# ESP-12E_Breakout_SMT.net
KiCad netlist of a schematic drawn in EAGLE
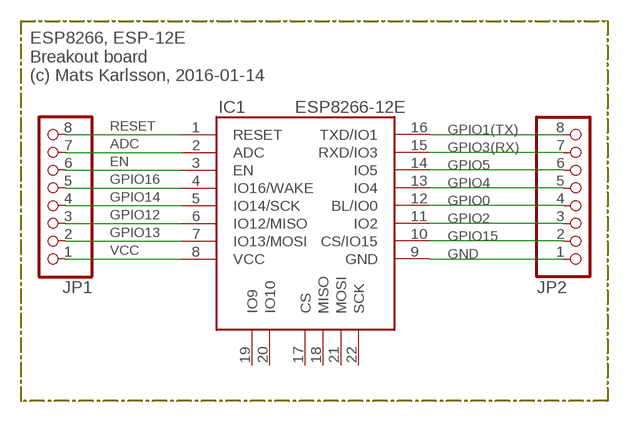
[diagram p0: schematic, sheet 1]

(export (version "E")
  (design (tool "Eeschema 10.0.6"))
  (components
    (comp (ref "IC1")
      (value "ESP8266-12E")
      (footprint "eagle-import:ESP8266-12E")
      (libsource (lib "eagle-import") (part "ESP8266-12E"))
    )
    (comp (ref "JP1")
      (value "PINHD-1X81X08_SMT")
      (footprint "eagle-import:1X08_SMT")
      (libsource (lib "eagle-import") (part "PINHD-1X81X08_SMT"))
    )
    (comp (ref "JP2")
      (value "PINHD-1X81X08_SMT")
      (footprint "eagle-import:1X08_SMT")
      (libsource (lib "eagle-import") (part "PINHD-1X81X08_SMT"))
    )
  )
  (nets
    (net (code "1") (name "/ADC") (class "Default")
      (node (ref "IC1") (pin "2") (pinfunction "ADC_2") (pintype "bidirectional"))
      (node (ref "JP1") (pin "7") (pinfunction "7_7") (pintype "passive"))
    )
    (net (code "2") (name "/EN") (class "Default")
      (node (ref "IC1") (pin "3") (pinfunction "EN_3") (pintype "bidirectional"))
      (node (ref "JP1") (pin "6") (pinfunction "6_6") (pintype "passive"))
    )
    (net (code "3") (name "/GND") (class "Default")
      (node (ref "IC1") (pin "9") (pinfunction "GND_9") (pintype "power_in"))
      (node (ref "JP2") (pin "1") (pinfunction "1_1") (pintype "passive"))
    )
    (net (code "4") (name "/GPIO0") (class "Default")
      (node (ref "IC1") (pin "12") (pinfunction "BL/IO0_12") (pintype "bidirectional"))
      (node (ref "JP2") (pin "4") (pinfunction "4_4") (pintype "passive"))
    )
    (net (code "5") (name "/GPIO1(TX)") (class "Default")
      (node (ref "IC1") (pin "16") (pinfunction "TXD/IO1_16") (pintype "bidirectional"))
      (node (ref "JP2") (pin "8") (pinfunction "8_8") (pintype "passive"))
    )
    (net (code "6") (name "/GPIO2") (class "Default")
      (node (ref "IC1") (pin "11") (pinfunction "IO2_11") (pintype "bidirectional"))
      (node (ref "JP2") (pin "3") (pinfunction "3_3") (pintype "passive"))
    )
    (net (code "7") (name "/GPIO3(RX)") (class "Default")
      (node (ref "IC1") (pin "15") (pinfunction "RXD/IO3_15") (pintype "bidirectional"))
      (node (ref "JP2") (pin "7") (pinfunction "7_7") (pintype "passive"))
    )
    (net (code "8") (name "/GPIO4") (class "Default")
      (node (ref "IC1") (pin "13") (pinfunction "IO4_13") (pintype "bidirectional"))
      (node (ref "JP2") (pin "5") (pinfunction "5_5") (pintype "passive"))
    )
    (net (code "9") (name "/GPIO5") (class "Default")
      (node (ref "IC1") (pin "14") (pinfunction "IO5_14") (pintype "bidirectional"))
      (node (ref "JP2") (pin "6") (pinfunction "6_6") (pintype "passive"))
    )
    (net (code "10") (name "/GPIO12") (class "Default")
      (node (ref "IC1") (pin "6") (pinfunction "IO12/MISO_6") (pintype "bidirectional"))
      (node (ref "JP1") (pin "3") (pinfunction "3_3") (pintype "passive"))
    )
    (net (code "11") (name "/GPIO13") (class "Default")
      (node (ref "IC1") (pin "7") (pinfunction "IO13/MOSI_7") (pintype "bidirectional"))
      (node (ref "JP1") (pin "2") (pinfunction "2_2") (pintype "passive"))
    )
    (net (code "12") (name "/GPIO14") (class "Default")
      (node (ref "IC1") (pin "5") (pinfunction "IO14/SCK_5") (pintype "bidirectional"))
      (node (ref "JP1") (pin "4") (pinfunction "4_4") (pintype "passive"))
    )
    (net (code "13") (name "/GPIO15") (class "Default")
      (node (ref "IC1") (pin "10") (pinfunction "CS/IO15_10") (pintype "bidirectional"))
      (node (ref "JP2") (pin "2") (pinfunction "2_2") (pintype "passive"))
    )
    (net (code "14") (name "/GPIO16") (class "Default")
      (node (ref "IC1") (pin "4") (pinfunction "IO16/WAKE_4") (pintype "bidirectional"))
      (node (ref "JP1") (pin "5") (pinfunction "5_5") (pintype "passive"))
    )
    (net (code "15") (name "/RESET") (class "Default")
      (node (ref "IC1") (pin "1") (pinfunction "RESET_1") (pintype "bidirectional"))
      (node (ref "JP1") (pin "8") (pinfunction "8_8") (pintype "passive"))
    )
    (net (code "16") (name "/VCC") (class "Default")
      (node (ref "IC1") (pin "8") (pinfunction "VCC_8") (pintype "power_in"))
      (node (ref "JP1") (pin "1") (pinfunction "1_1") (pintype "passive"))
    )
    (net (code "17") (name "unconnected-(IC1-CS-Pad17)") (class "Default")
      (node (ref "IC1") (pin "17") (pinfunction "CS_17") (pintype "bidirectional"))
    )
    (net (code "18") (name "unconnected-(IC1-IO9-Pad19)") (class "Default")
      (node (ref "IC1") (pin "19") (pinfunction "IO9_19") (pintype "bidirectional"))
    )
    (net (code "19") (name "unconnected-(IC1-IO10-Pad20)") (class "Default")
      (node (ref "IC1") (pin "20") (pinfunction "IO10_20") (pintype "bidirectional"))
    )
    (net (code "20") (name "unconnected-(IC1-MISO-Pad18)") (class "Default")
      (node (ref "IC1") (pin "18") (pinfunction "MISO_18") (pintype "bidirectional"))
    )
    (net (code "21") (name "unconnected-(IC1-MOSI-Pad21)") (class "Default")
      (node (ref "IC1") (pin "21") (pinfunction "MOSI_21") (pintype "bidirectional"))
    )
    (net (code "22") (name "unconnected-(IC1-SCK-Pad22)") (class "Default")
      (node (ref "IC1") (pin "22") (pinfunction "SCK_22") (pintype "bidirectional"))
    )
  )
)
